# USB.net
KiCad netlist of a schematic drawn in EAGLE
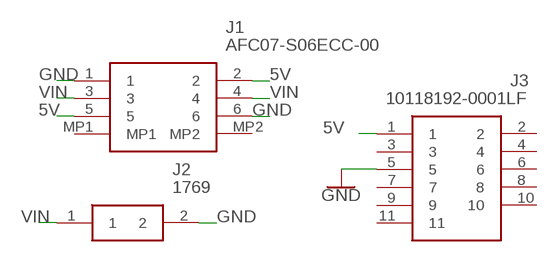
[diagram p0: schematic, sheet 1]

(export (version "E")
  (design (tool "Eeschema 10.0.6"))
  (components
    (comp (ref "J1")
      (value "AFC07-S06ECC-00")
      (footprint "eagle-import:AFC07S06ECC00")
      (libsource (lib "eagle-import") (part "AFC07-S06ECC-00"))
    )
    (comp (ref "J2")
      (value "1769")
      (footprint "eagle-import:1769")
      (fields (field (name "MOUSER_PART_NUMBER") "485-1769"))
      (libsource (lib "eagle-import") (part "1769"))
    )
    (comp (ref "J3")
      (value "10118192-0001LF")
      (footprint "eagle-import:101181920001LF")
      (fields (field (name "MOUSER_PART_NUMBER") "649-10118192-0001LF"))
      (libsource (lib "eagle-import") (part "10118192-0001LF"))
    )
  )
  (nets
    (net (code "1") (name "/5V") (class "Default")
      (node (ref "J1") (pin "2") (pinfunction "2_2") (pintype "bidirectional"))
      (node (ref "J1") (pin "5") (pinfunction "5_5") (pintype "bidirectional"))
      (node (ref "J3") (pin "1") (pinfunction "1_1") (pintype "bidirectional"))
    )
    (net (code "2") (name "/VIN") (class "Default")
      (node (ref "J1") (pin "3") (pinfunction "3_3") (pintype "bidirectional"))
      (node (ref "J1") (pin "4") (pinfunction "4_4") (pintype "bidirectional"))
      (node (ref "J2") (pin "1") (pinfunction "1_1") (pintype "bidirectional"))
    )
    (net (code "3") (name "GND") (class "Default")
      (node (ref "J1") (pin "1") (pinfunction "1_1") (pintype "bidirectional"))
      (node (ref "J1") (pin "6") (pinfunction "6_6") (pintype "bidirectional"))
      (node (ref "J2") (pin "2") (pinfunction "2_2") (pintype "bidirectional"))
      (node (ref "J3") (pin "5") (pinfunction "5_5") (pintype "bidirectional"))
    )
    (net (code "4") (name "unconnected-(J1-PadMP1)") (class "Default")
      (node (ref "J1") (pin "MP1") (pinfunction "MP1_MP1") (pintype "bidirectional"))
    )
    (net (code "5") (name "unconnected-(J1-PadMP2)") (class "Default")
      (node (ref "J1") (pin "MP2") (pinfunction "MP2_MP2") (pintype "bidirectional"))
    )
    (net (code "6") (name "unconnected-(J3-Pad2)") (class "Default")
      (node (ref "J3") (pin "2") (pinfunction "2_2") (pintype "bidirectional"))
    )
    (net (code "7") (name "unconnected-(J3-Pad3)") (class "Default")
      (node (ref "J3") (pin "3") (pinfunction "3_3") (pintype "bidirectional"))
    )
    (net (code "8") (name "unconnected-(J3-Pad4)") (class "Default")
      (node (ref "J3") (pin "4") (pinfunction "4_4") (pintype "bidirectional"))
    )
    (net (code "9") (name "unconnected-(J3-Pad6)") (class "Default")
      (node (ref "J3") (pin "6") (pinfunction "6_6") (pintype "bidirectional"))
    )
    (net (code "10") (name "unconnected-(J3-Pad7)") (class "Default")
      (node (ref "J3") (pin "7") (pinfunction "7_7") (pintype "bidirectional"))
    )
    (net (code "11") (name "unconnected-(J3-Pad8)") (class "Default")
      (node (ref "J3") (pin "8") (pinfunction "8_8") (pintype "bidirectional"))
    )
    (net (code "12") (name "unconnected-(J3-Pad9)") (class "Default")
      (node (ref "J3") (pin "9") (pinfunction "9_9") (pintype "bidirectional"))
    )
    (net (code "13") (name "unconnected-(J3-Pad10)") (class "Default")
      (node (ref "J3") (pin "10") (pinfunction "10_10") (pintype "bidirectional"))
    )
    (net (code "14") (name "unconnected-(J3-Pad11)") (class "Default")
      (node (ref "J3") (pin "11") (pinfunction "11_11") (pintype "bidirectional"))
    )
  )
)
